# Indicators.net
KiCad netlist of a schematic drawn in Altium Designer
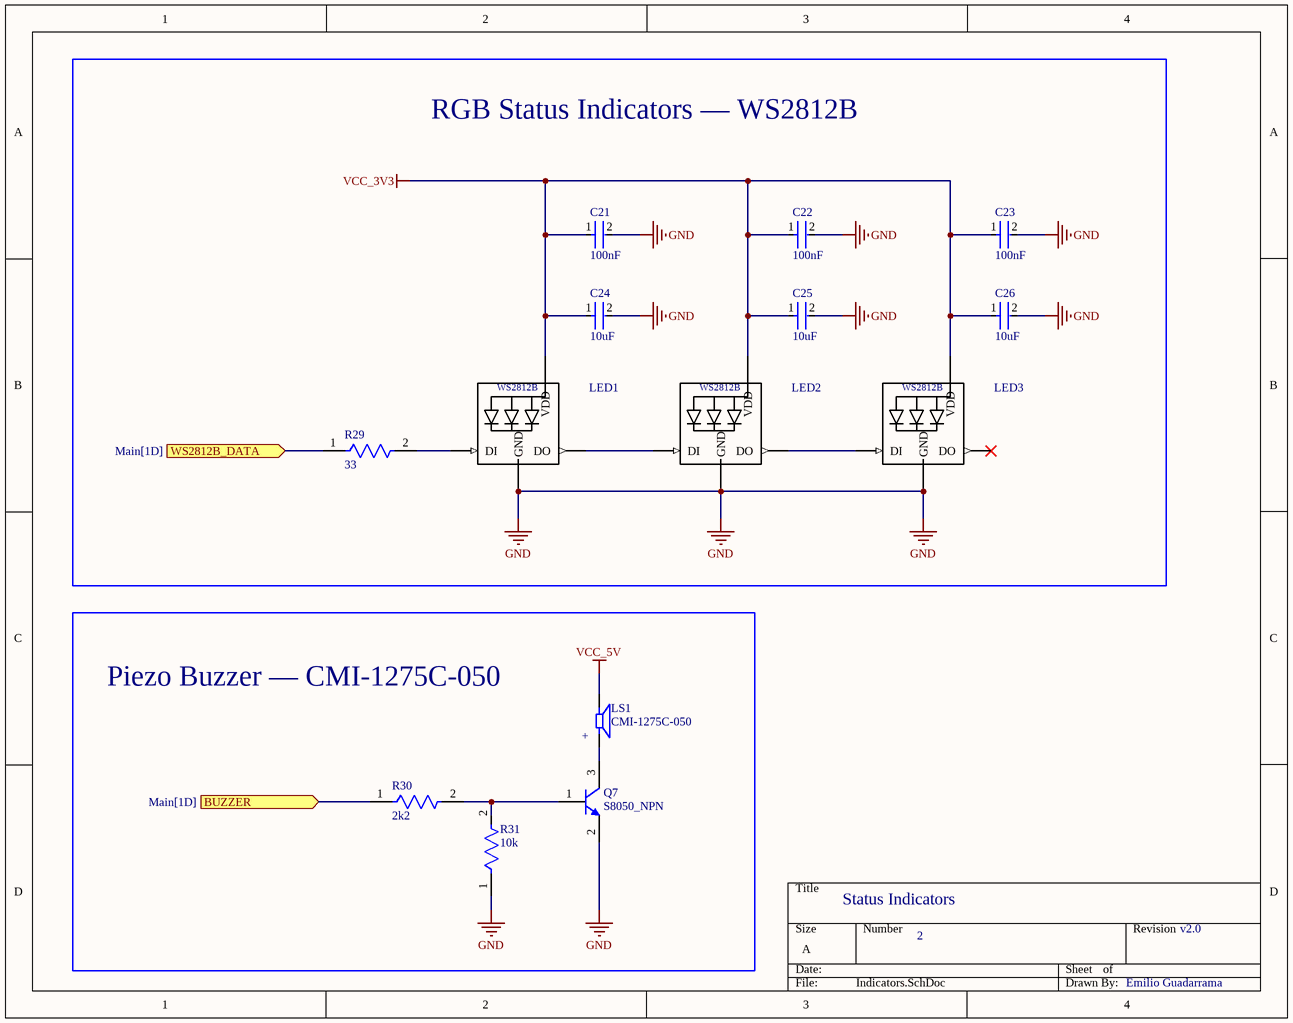
[diagram p0: Indicators.SchDoc]

(export (version "E")
  (design (tool "Eeschema 10.0.6"))
  (components
    (comp (ref "C21")
      (value "100nF")
      (footprint "FP-C0805C-DN-MFG")
      (description "CAP CER 0.1UF 50V X7R 0805")
      (fields
        (field (name "MANUFACTURER PART NUMBER") "C0805C104K5RACTU")
        (field (name "MANUFACTURER") "KEMET")
      )
      (libsource (lib "Altium Content Vault") (part "b4654b650e69147ec39a6b967a45e02"))
    )
    (comp (ref "C22")
      (value "100nF")
      (footprint "FP-C0805C-DN-MFG")
      (description "CAP CER 0.1UF 50V X7R 0805")
      (fields
        (field (name "MANUFACTURER PART NUMBER") "C0805C104K5RACTU")
        (field (name "MANUFACTURER") "KEMET")
      )
      (libsource (lib "Altium Content Vault") (part "b4654b650e69147ec39a6b967a45e02"))
    )
    (comp (ref "C23")
      (value "100nF")
      (footprint "FP-C0805C-DN-MFG")
      (description "CAP CER 0.1UF 50V X7R 0805")
      (fields
        (field (name "MANUFACTURER PART NUMBER") "C0805C104K5RACTU")
        (field (name "MANUFACTURER") "KEMET")
      )
      (libsource (lib "Altium Content Vault") (part "b4654b650e69147ec39a6b967a45e02"))
    )
    (comp (ref "C24")
      (value "10uF")
      (footprint "FP-C0805C-DN-MFG")
      (description "CAP CER 0.1UF 50V X7R 0805")
      (fields
        (field (name "MANUFACTURER PART NUMBER") "C0805C104K5RACTU")
        (field (name "MANUFACTURER") "KEMET")
      )
      (libsource (lib "Altium Content Vault") (part "b4654b650e69147ec39a6b967a45e02"))
    )
    (comp (ref "C25")
      (value "10uF")
      (footprint "FP-C0805C-DN-MFG")
      (description "CAP CER 0.1UF 50V X7R 0805")
      (fields
        (field (name "MANUFACTURER PART NUMBER") "C0805C104K5RACTU")
        (field (name "MANUFACTURER") "KEMET")
      )
      (libsource (lib "Altium Content Vault") (part "b4654b650e69147ec39a6b967a45e02"))
    )
    (comp (ref "C26")
      (value "10uF")
      (footprint "FP-C0805C-DN-MFG")
      (description "CAP CER 0.1UF 50V X7R 0805")
      (fields
        (field (name "MANUFACTURER PART NUMBER") "C0805C104K5RACTU")
        (field (name "MANUFACTURER") "KEMET")
      )
      (libsource (lib "Altium Content Vault") (part "b4654b650e69147ec39a6b967a45e02"))
    )
    (comp (ref "LED1")
      (value "WS2812B")
      (footprint "*WS2812B_WS2812B(Primary)")
      (description "Intelligent control LED integrated light source")
      (fields (field (name "MF") "Worldsemi"))
      (libsource (lib "LED_RGB_WS2812B") (part "WS2812B"))
    )
    (comp (ref "LED2")
      (value "WS2812B")
      (footprint "*WS2812B_WS2812B(Primary)")
      (description "Intelligent control LED integrated light source")
      (fields (field (name "MF") "Worldsemi"))
      (libsource (lib "LED_RGB_WS2812B") (part "WS2812B"))
    )
    (comp (ref "LED3")
      (value "WS2812B")
      (footprint "*WS2812B_WS2812B(Primary)")
      (description "Intelligent control LED integrated light source")
      (fields (field (name "MF") "Worldsemi"))
      (libsource (lib "LED_RGB_WS2812B") (part "WS2812B"))
    )
    (comp (ref "LS1")
      (value "CMI-1275C-050")
      (footprint "CUI_CMI-1275C-050")
      (description "12 mm, 5 Vdc, 90 dB, 3.1 kHz, Through Hole, Magnetic Audio Indicator Buzzer")
      (fields (field (name "MF") "Same Sky"))
      (libsource (lib "BUZZER_CMI-1275C-050") (part "CMI-1275C-050"))
    )
    (comp (ref "Q7")
      (value "S8050_NPN")
      (footprint "PCBComponent_1")
      (libsource (lib "NPN_8050") (part "Component_1"))
    )
    (comp (ref "R29")
      (value "33")
      (footprint "FP-MCT0603-IPC_A")
      (description "RES SMD 100 OHM 1% 1/8W 0603")
      (fields (field (name "TOLERANCE") "0.1%"))
      (libsource (lib "Altium Content Vault") (part "1029c3af85768c4190bb7ad29bc67b5"))
    )
    (comp (ref "R30")
      (value "2k2")
      (footprint "FP-MCT0603-IPC_A")
      (description "RES SMD 100 OHM 1% 1/8W 0603")
      (fields (field (name "TOLERANCE") "0.1%"))
      (libsource (lib "Altium Content Vault") (part "1029c3af85768c4190bb7ad29bc67b5"))
    )
    (comp (ref "R31")
      (value "10k")
      (footprint "FP-MCT0603-IPC_A")
      (description "RES SMD 100 OHM 1% 1/8W 0603")
      (fields (field (name "TOLERANCE") "0.1%"))
      (libsource (lib "Altium Content Vault") (part "1029c3af85768c4190bb7ad29bc67b5"))
    )
  )
  (nets
    (net (code "1") (name "/BUZZER") (class "Default")
      (node (ref "R30") (pin "1") (pinfunction "1_1") (pintype "passive"))
    )
    (net (code "2") (name "/WS2812B_DATA") (class "Default")
      (node (ref "R29") (pin "1") (pinfunction "1_1") (pintype "passive"))
    )
    (net (code "3") (name "GND") (class "Default")
      (node (ref "C21") (pin "2") (pinfunction "2_2") (pintype "passive"))
      (node (ref "C22") (pin "2") (pinfunction "2_2") (pintype "passive"))
      (node (ref "C23") (pin "2") (pinfunction "2_2") (pintype "passive"))
      (node (ref "C24") (pin "2") (pinfunction "2_2") (pintype "passive"))
      (node (ref "C25") (pin "2") (pinfunction "2_2") (pintype "passive"))
      (node (ref "C26") (pin "2") (pinfunction "2_2") (pintype "passive"))
      (node (ref "LED1") (pin "3-GND") (pinfunction "GND_3-GND") (pintype "power_in"))
      (node (ref "LED2") (pin "3-GND") (pinfunction "GND_3-GND") (pintype "power_in"))
      (node (ref "LED3") (pin "3-GND") (pinfunction "GND_3-GND") (pintype "power_in"))
      (node (ref "Q7") (pin "2") (pinfunction "E_2") (pintype "passive"))
      (node (ref "R31") (pin "1") (pinfunction "1_1") (pintype "passive"))
    )
    (net (code "4") (name "Net-(LED1-DI)") (class "Default")
      (node (ref "LED1") (pin "4-DIN") (pinfunction "DI_4-DIN") (pintype "input"))
      (node (ref "R29") (pin "2") (pinfunction "2_2") (pintype "passive"))
    )
    (net (code "5") (name "Net-(LED1-DO)") (class "Default")
      (node (ref "LED1") (pin "2-DOUT") (pinfunction "DO_2-DOUT") (pintype "output"))
      (node (ref "LED2") (pin "4-DIN") (pinfunction "DI_4-DIN") (pintype "input"))
    )
    (net (code "6") (name "Net-(LED2-DO)") (class "Default")
      (node (ref "LED2") (pin "2-DOUT") (pinfunction "DO_2-DOUT") (pintype "output"))
      (node (ref "LED3") (pin "4-DIN") (pinfunction "DI_4-DIN") (pintype "input"))
    )
    (net (code "7") (name "Net-(Q7-B)") (class "Default")
      (node (ref "Q7") (pin "1") (pinfunction "B_1") (pintype "passive"))
      (node (ref "R30") (pin "2") (pinfunction "2_2") (pintype "passive"))
      (node (ref "R31") (pin "2") (pinfunction "2_2") (pintype "passive"))
    )
    (net (code "8") (name "Net-(Q7-C)") (class "Default")
      (node (ref "LS1") (pin "P") (pinfunction "P_P") (pintype "passive"))
      (node (ref "Q7") (pin "3") (pinfunction "C_3") (pintype "passive"))
    )
    (net (code "9") (name "VCC_3V3") (class "Default")
      (node (ref "C21") (pin "1") (pinfunction "1_1") (pintype "passive"))
      (node (ref "C22") (pin "1") (pinfunction "1_1") (pintype "passive"))
      (node (ref "C23") (pin "1") (pinfunction "1_1") (pintype "passive"))
      (node (ref "C24") (pin "1") (pinfunction "1_1") (pintype "passive"))
      (node (ref "C25") (pin "1") (pinfunction "1_1") (pintype "passive"))
      (node (ref "C26") (pin "1") (pinfunction "1_1") (pintype "passive"))
      (node (ref "LED1") (pin "1-VDD") (pinfunction "VDD_1-VDD") (pintype "power_in"))
      (node (ref "LED2") (pin "1-VDD") (pinfunction "VDD_1-VDD") (pintype "power_in"))
      (node (ref "LED3") (pin "1-VDD") (pinfunction "VDD_1-VDD") (pintype "power_in"))
    )
    (net (code "10") (name "VCC_5V") (class "Default")
      (node (ref "LS1") (pin "N") (pinfunction "N_N") (pintype "passive"))
    )
    (net (code "11") (name "unconnected-(LED3-DO-Pad2-DOUT)") (class "Default")
      (node (ref "LED3") (pin "2-DOUT") (pinfunction "DO_2-DOUT") (pintype "output+no_connect"))
    )
  )
)
